# CH32F207VCT6-R0.net
KiCad netlist of a schematic drawn in Altium Designer
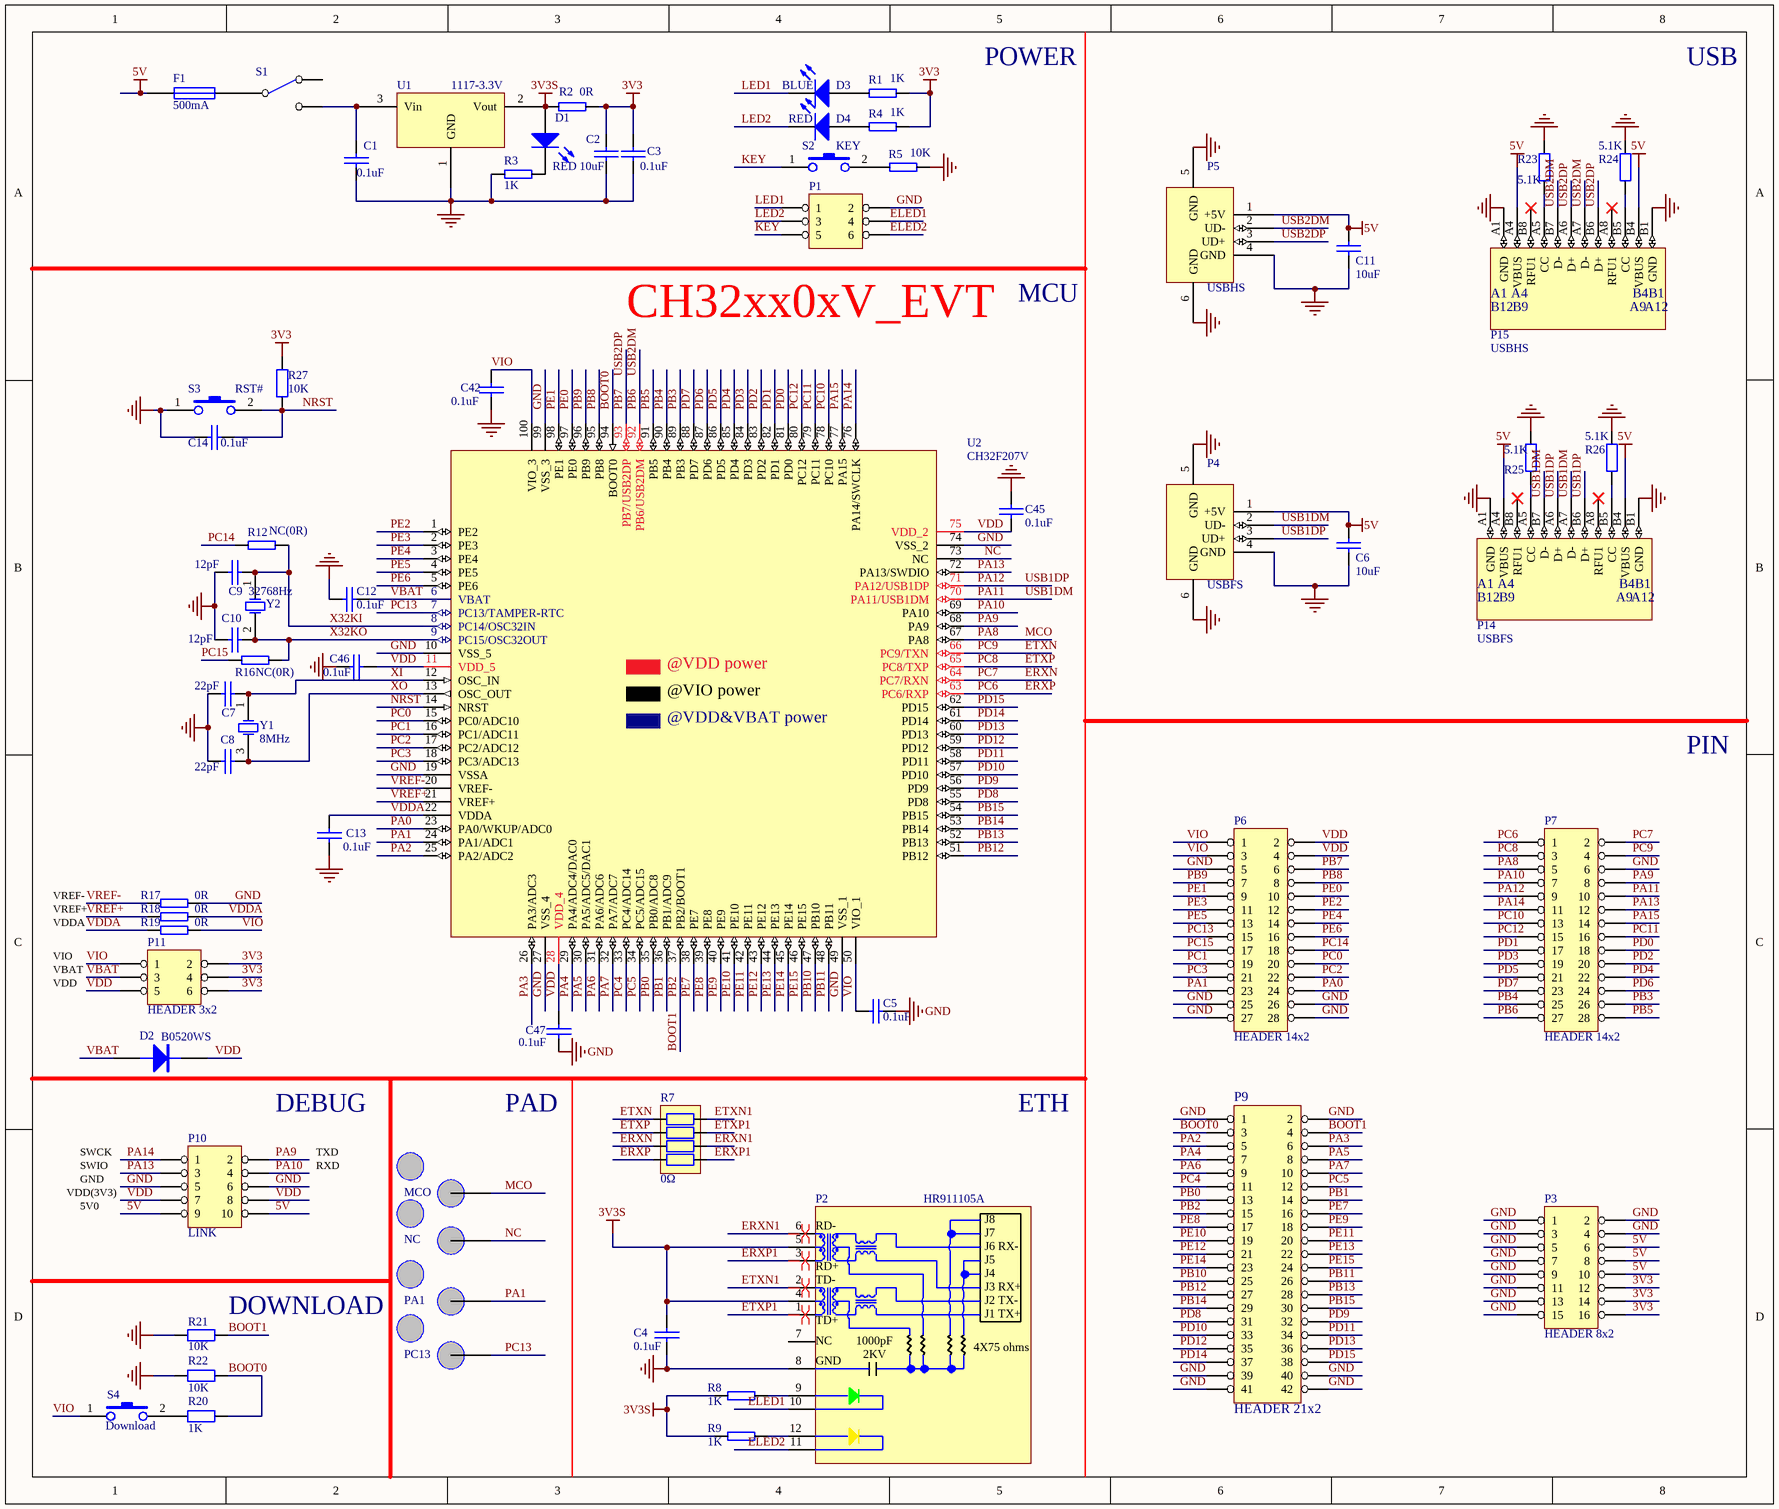
[diagram p0: CH32F207VCT6-R0.SchDoc]

(export (version "E")
  (design (tool "Eeschema 10.0.6"))
  (components
    (comp (ref "C1")
      (value "0.1uF")
      (footprint "0603_C")
      (description "Capacitor")
      (libsource (lib "*") (part "CAP"))
    )
    (comp (ref "C2")
      (value "10uF")
      (footprint "3216_C")
      (description "Capacitor")
      (libsource (lib "*") (part "CAP"))
    )
    (comp (ref "C3")
      (value "0.1uF")
      (footprint "0603_C")
      (description "Capacitor")
      (libsource (lib "*") (part "CAP"))
    )
    (comp (ref "C4")
      (value "0.1uF")
      (footprint "0603_C")
      (description "Capacitor")
      (libsource (lib "*") (part "CAP"))
    )
    (comp (ref "C5")
      (value "0.1uF")
      (footprint "0603_C")
      (description "Capacitor")
      (libsource (lib "*") (part "CAP"))
    )
    (comp (ref "C6")
      (value "10uF")
      (footprint "3216_C")
      (description "Capacitor")
      (libsource (lib "") (part "CAP_1"))
    )
    (comp (ref "C7")
      (value "22pF")
      (footprint "0603_C")
      (description "Capacitor")
      (libsource (lib "*") (part "CAP"))
    )
    (comp (ref "C8")
      (value "22pF")
      (footprint "0603_C")
      (description "Capacitor")
      (libsource (lib "*") (part "CAP"))
    )
    (comp (ref "C9")
      (value "12pF")
      (footprint "0603_C")
      (description "Capacitor")
      (libsource (lib "*") (part "CAP"))
    )
    (comp (ref "C10")
      (value "12pF")
      (footprint "0603_C")
      (description "Capacitor")
      (libsource (lib "*") (part "CAP"))
    )
    (comp (ref "C11")
      (value "10uF")
      (footprint "3216_C")
      (description "Capacitor")
      (libsource (lib "") (part "CAP_1"))
    )
    (comp (ref "C12")
      (value "0.1uF")
      (footprint "0603_C")
      (description "Capacitor")
      (libsource (lib "*") (part "CAP"))
    )
    (comp (ref "C13")
      (value "0.1uF")
      (footprint "0603_C")
      (description "Capacitor")
      (libsource (lib "*") (part "CAP"))
    )
    (comp (ref "C14")
      (value "0.1uF")
      (footprint "0603_C")
      (description "Capacitor")
      (libsource (lib "") (part "CAP_1"))
    )
    (comp (ref "C42")
      (value "0.1uF")
      (footprint "0603_C")
      (description "Capacitor")
      (libsource (lib "*") (part "CAP"))
    )
    (comp (ref "C45")
      (value "0.1uF")
      (footprint "0603_C")
      (description "Capacitor")
      (libsource (lib "*") (part "CAP"))
    )
    (comp (ref "C46")
      (value "0.1uF")
      (footprint "0603_C")
      (description "Capacitor")
      (libsource (lib "*") (part "CAP"))
    )
    (comp (ref "C47")
      (value "0.1uF")
      (footprint "0603_C")
      (description "Capacitor")
      (libsource (lib "*") (part "CAP"))
    )
    (comp (ref "D1")
      (value "RED")
      (footprint "0603+")
      (description "Typical INFRARED GaAs LED")
      (fields (field (name "PUBLISHER") "Altium Limited"))
      (libsource (lib "*") (part "LED0"))
    )
    (comp (ref "D2")
      (value "B0520WS")
      (footprint "SOD-323")
      (description "Diode")
      (libsource (lib "*") (part "DIODE"))
    )
    (comp (ref "D3")
      (value "BLUE")
      (footprint "0603+")
      (description "Typical INFRARED GaAs LED")
      (fields (field (name "PUBLISHER") "Altium Limited"))
      (libsource (lib "*") (part "LED0"))
    )
    (comp (ref "D4")
      (value "RED")
      (footprint "0603+")
      (description "Typical INFRARED GaAs LED")
      (fields (field (name "PUBLISHER") "Altium Limited"))
      (libsource (lib "*") (part "LED0"))
    )
    (comp (ref "F1")
      (value "500mA")
      (footprint "0805")
      (description "Fuse")
      (libsource (lib "wch_sch_others") (part "FUSE1"))
    )
    (comp (ref "MCO")
      (value "Testpoint")
      (footprint "TESTPOINT1")
      (description "测试点")
      (libsource (lib "wch_sch_others") (part "Testpoint"))
    )
    (comp (ref "NC")
      (value "Testpoint")
      (footprint "TESTPOINT1")
      (description "测试点")
      (libsource (lib "wch_sch_others") (part "Testpoint"))
    )
    (comp (ref "P1")
      (value "IO")
      (footprint "MYPCB:IDC6-2.54mm")
      (description "Header, 3-Pin, Dual row")
      (libsource (lib "wch_sch_others") (part "HEADER 3x2"))
    )
    (comp (ref "P2") (value "HR911105A") (footprint "HR911105A") (libsource (lib "*") (part "HR911105A")))
    (comp (ref "P3")
      (value "HEADER 8x2")
      (footprint "MYPCB:IDC16-2.54mm")
      (description "Header, 8-Pin, Dual row")
      (libsource (lib "wch_sch_others") (part "HEADER 8x2"))
    )
    (comp (ref "P4")
      (value "USBFS")
      (footprint "USBAF")
      (description "USB Port")
      (libsource (lib "*") (part "USB"))
    )
    (comp (ref "P5")
      (value "USBHS")
      (footprint "USBAF")
      (description "USB Port")
      (libsource (lib "*") (part "USB"))
    )
    (comp (ref "P6")
      (value "HEADER 14x2")
      (footprint "MYPCB:IDC28-2.54MM")
      (description "Header, 14-Pin, Dual row")
      (libsource (lib "wch_sch_others") (part "HEADER 14x2"))
    )
    (comp (ref "P7")
      (value "HEADER 14x2")
      (footprint "MYPCB:IDC28-2.54MM")
      (description "Header, 14-Pin, Dual row")
      (libsource (lib "wch_sch_others") (part "HEADER 14x2"))
    )
    (comp (ref "P9")
      (value "HEADER 21x2")
      (footprint "MYPCB:IDC42-2.54MM")
      (description "Header, 21-Pin, Dual row")
      (libsource (lib "wch_sch_others") (part "HEADER 21x2"))
    )
    (comp (ref "P10")
      (value "LINK")
      (footprint "MYPCB:IDC10-2.54mm")
      (description "Header, 5-Pin, Dual row")
      (libsource (lib "wch_sch_others") (part "HEADER 5x2"))
    )
    (comp (ref "P11")
      (value "HEADER 3x2")
      (footprint "MYPCB:IDC6-2.54mm")
      (description "Header, 3-Pin, Dual row")
      (libsource (lib "wch_sch_others") (part "HEADER 3x2"))
    )
    (comp (ref "P14")
      (value "USBFS")
      (footprint "TYPE-C-Receptacle-2.0")
      (libsource (lib "*") (part "TYPE-C1"))
    )
    (comp (ref "P15")
      (value "USBHS")
      (footprint "TYPE-C-Receptacle-2.0")
      (libsource (lib "*") (part "TYPE-C1"))
    )
    (comp (ref "PA1")
      (value "Testpoint")
      (footprint "TESTPOINT1")
      (description "测试点")
      (libsource (lib "wch_sch_others") (part "Testpoint"))
    )
    (comp (ref "PC13")
      (value "Testpoint")
      (footprint "TESTPOINT1")
      (description "测试点")
      (libsource (lib "wch_sch_others") (part "Testpoint"))
    )
    (comp (ref "R1") (value "1K") (footprint "0603") (libsource (lib "wch_sch_others") (part "RES")))
    (comp (ref "R2") (value "0R") (footprint "0603") (libsource (lib "wch_sch_others") (part "RES")))
    (comp (ref "R3") (value "1K") (footprint "0603") (libsource (lib "wch_sch_others") (part "RES")))
    (comp (ref "R4") (value "1K") (footprint "0603") (libsource (lib "wch_sch_others") (part "RES")))
    (comp (ref "R5") (value "10K") (footprint "0603") (libsource (lib "wch_sch_others") (part "RES")))
    (comp (ref "R7")
      (value "0Ω")
      (footprint "RCA-8P4R-0603")
      (description "贴片网络排阻")
      (fields (field (name "版权归属") "源创客"))
      (libsource (lib "wch_sch_others") (part "R-8P4R"))
    )
    (comp (ref "R8") (value "1K") (footprint "0603") (libsource (lib "wch_sch_others") (part "RES")))
    (comp (ref "R9") (value "1K") (footprint "0603") (libsource (lib "wch_sch_others") (part "RES")))
    (comp (ref "R12") (value "NC(0R)") (footprint "0603") (libsource (lib "wch_sch_others") (part "RES")))
    (comp (ref "R16") (value "NC(0R)") (footprint "0603") (libsource (lib "wch_sch_others") (part "RES")))
    (comp (ref "R17") (value "0R") (footprint "0603") (libsource (lib "*") (part "R")))
    (comp (ref "R18") (value "0R") (footprint "0603") (libsource (lib "*") (part "R")))
    (comp (ref "R19") (value "0R") (footprint "0603") (libsource (lib "*") (part "R")))
    (comp (ref "R20")
      (value "1K")
      (footprint "0603")
      (description "Resistor")
      (fields (field (name "PUBLISHER") "Altium Limited"))
      (libsource (lib "Miscellaneous Devices") (part "Res2"))
    )
    (comp (ref "R21")
      (value "10K")
      (footprint "0603")
      (description "Resistor")
      (fields (field (name "PUBLISHER") "Altium Limited"))
      (libsource (lib "Miscellaneous Devices") (part "Res2"))
    )
    (comp (ref "R22")
      (value "10K")
      (footprint "0603")
      (description "Resistor")
      (fields (field (name "PUBLISHER") "Altium Limited"))
      (libsource (lib "Miscellaneous Devices") (part "Res2"))
    )
    (comp (ref "R23")
      (value "5.1K")
      (footprint "0603")
      (description "Resistor")
      (libsource (lib "") (part "Res2_1"))
    )
    (comp (ref "R24")
      (value "5.1K")
      (footprint "0603")
      (description "Resistor")
      (libsource (lib "") (part "Res2_1"))
    )
    (comp (ref "R25")
      (value "5.1K")
      (footprint "0603")
      (description "Resistor")
      (libsource (lib "") (part "Res2_1"))
    )
    (comp (ref "R26")
      (value "5.1K")
      (footprint "0603")
      (description "Resistor")
      (libsource (lib "") (part "Res2_1"))
    )
    (comp (ref "R27")
      (value "10K")
      (footprint "0603")
      (description "Resistor")
      (fields (field (name "PUBLISHER") "Altium Limited"))
      (libsource (lib "") (part "Res2_1"))
    )
    (comp (ref "S1") (value "SW SPDT") (footprint "KEY2") (libsource (lib "*") (part "SW SPDT")))
    (comp (ref "S2")
      (value "KEY")
      (footprint "SMD_6.1x3.65x2.5mm-KEY")
      (libsource (lib "wch_sch_others") (part "KEY1"))
    )
    (comp (ref "S3")
      (value "RST#")
      (footprint "SMD_6.1x3.65x2.5mm-KEY")
      (libsource (lib "wch_sch_others") (part "KEY1"))
    )
    (comp (ref "S4")
      (value "Download")
      (footprint "SMD_6.1x3.65x2.5mm-KEY")
      (libsource (lib "wch_sch_others") (part "KEY1"))
    )
    (comp (ref "U1")
      (value "1117-3.3V")
      (footprint "SOT-223")
      (libsource (lib "wch_sch_others") (part "1117-3.3V"))
    )
    (comp (ref "U2")
      (value "CH32F207V")
      (footprint "LQFP100")
      (description "ARM M3 HD-MCU, 144MHz, USB_480M, USB OTG, 1000M Ethernet MAC, 2*CAN")
      (libsource (lib "CHXXX") (part "CH32F207V"))
    )
    (comp (ref "Y1")
      (value "8MHz")
      (footprint "XT3225")
      (description "Crystal Oscillator")
      (fields (field (name "PUBLISHER") "Altium Limited"))
      (libsource (lib "*") (part "XTAL"))
    )
    (comp (ref "Y2")
      (value "32768Hz")
      (footprint "FC-135")
      (description "Crystal Oscillator")
      (fields (field (name "PUBLISHER") "Altium Limited"))
      (libsource (lib "") (part "XTAL_1"))
    )
  )
  (nets
    (net (code "2") (name "/BOOT0") (class "Default")
      (node (ref "P9") (pin "3") (pinfunction "3_3") (pintype "passive"))
      (node (ref "R20") (pin "1") (pinfunction "1_1") (pintype "passive"))
      (node (ref "R22") (pin "1") (pinfunction "1_1") (pintype "passive"))
      (node (ref "U2") (pin "94") (pinfunction "BOOT0_94") (pintype "input"))
    )
    (net (code "3") (name "/BOOT1") (class "Default")
      (node (ref "P9") (pin "15") (pinfunction "15_15") (pintype "passive"))
      (node (ref "P9") (pin "4") (pinfunction "4_4") (pintype "passive"))
      (node (ref "R21") (pin "1") (pinfunction "1_1") (pintype "passive"))
      (node (ref "U2") (pin "37") (pinfunction "PB2/BOOT1_37") (pintype "bidirectional"))
    )
    (net (code "4") (name "/ELED1") (class "Default")
      (node (ref "P1") (pin "4") (pinfunction "4_4") (pintype "passive"))
      (node (ref "P2") (pin "10") (pintype "passive"))
    )
    (net (code "5") (name "/ELED2") (class "Default")
      (node (ref "P1") (pin "6") (pinfunction "6_6") (pintype "passive"))
      (node (ref "P2") (pin "11") (pintype "passive"))
    )
    (net (code "6") (name "/ERXN") (class "Default")
      (node (ref "P7") (pin "2") (pinfunction "2_2") (pintype "passive"))
      (node (ref "R7") (pin "3") (pinfunction "3_3") (pintype "passive"))
      (node (ref "U2") (pin "64") (pinfunction "PC7/RXN_64") (pintype "bidirectional"))
    )
    (net (code "7") (name "/ERXN1") (class "Default")
      (node (ref "P2") (pin "6") (pintype "passive"))
      (node (ref "R7") (pin "6") (pinfunction "6_6") (pintype "passive"))
    )
    (net (code "8") (name "/ERXP") (class "Default")
      (node (ref "P7") (pin "1") (pinfunction "1_1") (pintype "passive"))
      (node (ref "R7") (pin "4") (pinfunction "4_4") (pintype "passive"))
      (node (ref "U2") (pin "63") (pinfunction "PC6/RXP_63") (pintype "bidirectional"))
    )
    (net (code "9") (name "/ERXP1") (class "Default")
      (node (ref "P2") (pin "3") (pintype "passive"))
      (node (ref "R7") (pin "5") (pinfunction "5_5") (pintype "passive"))
    )
    (net (code "10") (name "/ETXN") (class "Default")
      (node (ref "P7") (pin "4") (pinfunction "4_4") (pintype "passive"))
      (node (ref "R7") (pin "1") (pinfunction "1_1") (pintype "passive"))
      (node (ref "U2") (pin "66") (pinfunction "PC9/TXN_66") (pintype "bidirectional"))
    )
    (net (code "11") (name "/ETXN1") (class "Default")
      (node (ref "P2") (pin "2") (pintype "passive"))
      (node (ref "R7") (pin "8") (pinfunction "8_8") (pintype "passive"))
    )
    (net (code "12") (name "/ETXP") (class "Default")
      (node (ref "P7") (pin "3") (pinfunction "3_3") (pintype "passive"))
      (node (ref "R7") (pin "2") (pinfunction "2_2") (pintype "passive"))
      (node (ref "U2") (pin "65") (pinfunction "PC8/TXP_65") (pintype "bidirectional"))
    )
    (net (code "13") (name "/ETXP1") (class "Default")
      (node (ref "P2") (pin "1") (pintype "passive"))
      (node (ref "R7") (pin "7") (pinfunction "7_7") (pintype "passive"))
    )
    (net (code "14") (name "/KEY") (class "Default")
      (node (ref "P1") (pin "5") (pinfunction "5_5") (pintype "passive"))
      (node (ref "S2") (pin "1") (pinfunction "1_1") (pintype "passive"))
    )
    (net (code "15") (name "/LED1") (class "Default")
      (node (ref "D3") (pin "2") (pinfunction "K_2") (pintype "passive"))
      (node (ref "P1") (pin "1") (pinfunction "1_1") (pintype "passive"))
    )
    (net (code "16") (name "/LED2") (class "Default")
      (node (ref "D4") (pin "2") (pinfunction "K_2") (pintype "passive"))
      (node (ref "P1") (pin "3") (pinfunction "3_3") (pintype "passive"))
    )
    (net (code "17") (name "/MCO") (class "Default")
      (node (ref "MCO") (pin "1") (pinfunction "point_1") (pintype "passive"))
      (node (ref "P7") (pin "5") (pinfunction "5_5") (pintype "passive"))
      (node (ref "U2") (pin "67") (pinfunction "PA8_67") (pintype "bidirectional"))
    )
    (net (code "18") (name "/NC") (class "Default")
      (node (ref "NC") (pin "1") (pinfunction "point_1") (pintype "passive"))
      (node (ref "U2") (pin "73") (pinfunction "NC_73") (pintype "tri_state"))
    )
    (net (code "19") (name "/NRST") (class "Default")
      (node (ref "C14") (pin "2") (pinfunction "2_2") (pintype "passive"))
      (node (ref "R27") (pin "1") (pinfunction "1_1") (pintype "passive"))
      (node (ref "S3") (pin "2") (pinfunction "2_2") (pintype "passive"))
      (node (ref "U2") (pin "14") (pinfunction "NRST_14") (pintype "input"))
    )
    (net (code "20") (name "/PA0") (class "Default")
      (node (ref "P6") (pin "24") (pinfunction "24_24") (pintype "passive"))
      (node (ref "U2") (pin "23") (pinfunction "PA0/WKUP/ADC0_23") (pintype "bidirectional"))
    )
    (net (code "21") (name "/PA1") (class "Default")
      (node (ref "P6") (pin "23") (pinfunction "23_23") (pintype "passive"))
      (node (ref "PA1") (pin "1") (pinfunction "point_1") (pintype "passive"))
      (node (ref "U2") (pin "24") (pinfunction "PA1/ADC1_24") (pintype "bidirectional"))
    )
    (net (code "22") (name "/PA2") (class "Default")
      (node (ref "P9") (pin "5") (pinfunction "5_5") (pintype "passive"))
      (node (ref "U2") (pin "25") (pinfunction "PA2/ADC2_25") (pintype "bidirectional"))
    )
    (net (code "23") (name "/PA3") (class "Default")
      (node (ref "P9") (pin "6") (pinfunction "6_6") (pintype "passive"))
      (node (ref "U2") (pin "26") (pinfunction "PA3/ADC3_26") (pintype "bidirectional"))
    )
    (net (code "24") (name "/PA4") (class "Default")
      (node (ref "P9") (pin "7") (pinfunction "7_7") (pintype "passive"))
      (node (ref "U2") (pin "29") (pinfunction "PA4/ADC4/DAC0_29") (pintype "bidirectional"))
    )
    (net (code "25") (name "/PA5") (class "Default")
      (node (ref "P9") (pin "8") (pinfunction "8_8") (pintype "passive"))
      (node (ref "U2") (pin "30") (pinfunction "PA5/ADC5/DAC1_30") (pintype "bidirectional"))
    )
    (net (code "26") (name "/PA6") (class "Default")
      (node (ref "P9") (pin "9") (pinfunction "9_9") (pintype "passive"))
      (node (ref "U2") (pin "31") (pinfunction "PA6/ADC6_31") (pintype "bidirectional"))
    )
    (net (code "27") (name "/PA7") (class "Default")
      (node (ref "P9") (pin "10") (pinfunction "10_10") (pintype "passive"))
      (node (ref "U2") (pin "32") (pinfunction "PA7/ADC7_32") (pintype "bidirectional"))
    )
    (net (code "28") (name "/PA9") (class "Default")
      (node (ref "P10") (pin "2") (pinfunction "2_2") (pintype "passive"))
      (node (ref "P7") (pin "8") (pinfunction "8_8") (pintype "passive"))
      (node (ref "U2") (pin "68") (pinfunction "PA9_68") (pintype "bidirectional"))
    )
    (net (code "29") (name "/PA10") (class "Default")
      (node (ref "P10") (pin "4") (pinfunction "4_4") (pintype "passive"))
      (node (ref "P7") (pin "7") (pinfunction "7_7") (pintype "passive"))
      (node (ref "U2") (pin "69") (pinfunction "PA10_69") (pintype "bidirectional"))
    )
    (net (code "30") (name "/PA11") (class "Default")
      (node (ref "P14") (pin "A7") (pinfunction "D-_A7") (pintype "bidirectional"))
      (node (ref "P14") (pin "B7") (pinfunction "D-_B7") (pintype "bidirectional"))
      (node (ref "P4") (pin "2") (pinfunction "UD-_2") (pintype "bidirectional"))
      (node (ref "P7") (pin "10") (pinfunction "10_10") (pintype "passive"))
      (node (ref "U2") (pin "70") (pinfunction "PA11/USB1DM_70") (pintype "bidirectional"))
    )
    (net (code "31") (name "/PA12") (class "Default")
      (node (ref "P14") (pin "A6") (pinfunction "D+_A6") (pintype "bidirectional"))
      (node (ref "P14") (pin "B6") (pinfunction "D+_B6") (pintype "bidirectional"))
      (node (ref "P4") (pin "3") (pinfunction "UD+_3") (pintype "bidirectional"))
      (node (ref "P7") (pin "9") (pinfunction "9_9") (pintype "passive"))
      (node (ref "U2") (pin "71") (pinfunction "PA12/USB1DP_71") (pintype "bidirectional"))
    )
    (net (code "32") (name "/PA13") (class "Default")
      (node (ref "P10") (pin "3") (pinfunction "3_3") (pintype "passive"))
      (node (ref "P7") (pin "12") (pinfunction "12_12") (pintype "passive"))
      (node (ref "U2") (pin "72") (pinfunction "PA13/SWDIO_72") (pintype "bidirectional"))
    )
    (net (code "33") (name "/PA14") (class "Default")
      (node (ref "P10") (pin "1") (pinfunction "1_1") (pintype "passive"))
      (node (ref "P7") (pin "11") (pinfunction "11_11") (pintype "passive"))
      (node (ref "U2") (pin "76") (pinfunction "PA14/SWCLK_76") (pintype "bidirectional"))
    )
    (net (code "34") (name "/PA15") (class "Default")
      (node (ref "P7") (pin "14") (pinfunction "14_14") (pintype "passive"))
      (node (ref "U2") (pin "77") (pinfunction "PA15_77") (pintype "bidirectional"))
    )
    (net (code "35") (name "/PB0") (class "Default")
      (node (ref "P9") (pin "13") (pinfunction "13_13") (pintype "passive"))
      (node (ref "U2") (pin "35") (pinfunction "PB0/ADC8_35") (pintype "bidirectional"))
    )
    (net (code "36") (name "/PB1") (class "Default")
      (node (ref "P9") (pin "14") (pinfunction "14_14") (pintype "passive"))
      (node (ref "U2") (pin "36") (pinfunction "PB1/ADC9_36") (pintype "bidirectional"))
    )
    (net (code "37") (name "/PB3") (class "Default")
      (node (ref "P7") (pin "26") (pinfunction "26_26") (pintype "passive"))
      (node (ref "U2") (pin "89") (pinfunction "PB3_89") (pintype "bidirectional"))
    )
    (net (code "38") (name "/PB4") (class "Default")
      (node (ref "P7") (pin "25") (pinfunction "25_25") (pintype "passive"))
      (node (ref "U2") (pin "90") (pinfunction "PB4_90") (pintype "bidirectional"))
    )
    (net (code "39") (name "/PB5") (class "Default")
      (node (ref "P7") (pin "28") (pinfunction "28_28") (pintype "passive"))
      (node (ref "U2") (pin "91") (pinfunction "PB5_91") (pintype "bidirectional"))
    )
    (net (code "40") (name "/PB6") (class "Default")
      (node (ref "P15") (pin "A7") (pinfunction "D-_A7") (pintype "bidirectional"))
      (node (ref "P15") (pin "B7") (pinfunction "D-_B7") (pintype "bidirectional"))
      (node (ref "P5") (pin "2") (pinfunction "UD-_2") (pintype "bidirectional"))
      (node (ref "P7") (pin "27") (pinfunction "27_27") (pintype "passive"))
      (node (ref "U2") (pin "92") (pinfunction "PB6/USB2DM_92") (pintype "bidirectional"))
    )
    (net (code "41") (name "/PB7") (class "Default")
      (node (ref "P15") (pin "A6") (pinfunction "D+_A6") (pintype "bidirectional"))
      (node (ref "P15") (pin "B6") (pinfunction "D+_B6") (pintype "bidirectional"))
      (node (ref "P5") (pin "3") (pinfunction "UD+_3") (pintype "bidirectional"))
      (node (ref "P6") (pin "6") (pinfunction "6_6") (pintype "passive"))
      (node (ref "U2") (pin "93") (pinfunction "PB7/USB2DP_93") (pintype "bidirectional"))
    )
    (net (code "42") (name "/PB8") (class "Default")
      (node (ref "P6") (pin "8") (pinfunction "8_8") (pintype "passive"))
      (node (ref "U2") (pin "95") (pinfunction "PB8_95") (pintype "bidirectional"))
    )
    (net (code "43") (name "/PB9") (class "Default")
      (node (ref "P6") (pin "7") (pinfunction "7_7") (pintype "passive"))
      (node (ref "U2") (pin "96") (pinfunction "PB9_96") (pintype "bidirectional"))
    )
    (net (code "44") (name "/PB10") (class "Default")
      (node (ref "P9") (pin "25") (pinfunction "25_25") (pintype "passive"))
      (node (ref "U2") (pin "47") (pinfunction "PB10_47") (pintype "bidirectional"))
    )
    (net (code "45") (name "/PB11") (class "Default")
      (node (ref "P9") (pin "26") (pinfunction "26_26") (pintype "passive"))
      (node (ref "U2") (pin "48") (pinfunction "PB11_48") (pintype "bidirectional"))
    )
    (net (code "46") (name "/PB12") (class "Default")
      (node (ref "P9") (pin "27") (pinfunction "27_27") (pintype "passive"))
      (node (ref "U2") (pin "51") (pinfunction "PB12_51") (pintype "bidirectional"))
    )
    (net (code "47") (name "/PB13") (class "Default")
      (node (ref "P9") (pin "28") (pinfunction "28_28") (pintype "passive"))
      (node (ref "U2") (pin "52") (pinfunction "PB13_52") (pintype "bidirectional"))
    )
    (net (code "48") (name "/PB14") (class "Default")
      (node (ref "P9") (pin "29") (pinfunction "29_29") (pintype "passive"))
      (node (ref "U2") (pin "53") (pinfunction "PB14_53") (pintype "bidirectional"))
    )
    (net (code "49") (name "/PB15") (class "Default")
      (node (ref "P9") (pin "30") (pinfunction "30_30") (pintype "passive"))
      (node (ref "U2") (pin "54") (pinfunction "PB15_54") (pintype "bidirectional"))
    )
    (net (code "50") (name "/PC0") (class "Default")
      (node (ref "P6") (pin "20") (pinfunction "20_20") (pintype "passive"))
      (node (ref "U2") (pin "15") (pinfunction "PC0/ADC10_15") (pintype "bidirectional"))
    )
    (net (code "51") (name "/PC1") (class "Default")
      (node (ref "P6") (pin "19") (pinfunction "19_19") (pintype "passive"))
      (node (ref "U2") (pin "16") (pinfunction "PC1/ADC11_16") (pintype "bidirectional"))
    )
    (net (code "52") (name "/PC2") (class "Default")
      (node (ref "P6") (pin "22") (pinfunction "22_22") (pintype "passive"))
      (node (ref "U2") (pin "17") (pinfunction "PC2/ADC12_17") (pintype "bidirectional"))
    )
    (net (code "53") (name "/PC3") (class "Default")
      (node (ref "P6") (pin "21") (pinfunction "21_21") (pintype "passive"))
      (node (ref "U2") (pin "18") (pinfunction "PC3/ADC13_18") (pintype "bidirectional"))
    )
    (net (code "54") (name "/PC4") (class "Default")
      (node (ref "P9") (pin "11") (pinfunction "11_11") (pintype "passive"))
      (node (ref "U2") (pin "33") (pinfunction "PC4/ADC14_33") (pintype "bidirectional"))
    )
    (net (code "55") (name "/PC5") (class "Default")
      (node (ref "P9") (pin "12") (pinfunction "12_12") (pintype "passive"))
      (node (ref "U2") (pin "34") (pinfunction "PC5/ADC15_34") (pintype "bidirectional"))
    )
    (net (code "56") (name "/PC10") (class "Default")
      (node (ref "P7") (pin "13") (pinfunction "13_13") (pintype "passive"))
      (node (ref "U2") (pin "78") (pinfunction "PC10_78") (pintype "bidirectional"))
    )
    (net (code "57") (name "/PC11") (class "Default")
      (node (ref "P7") (pin "16") (pinfunction "16_16") (pintype "passive"))
      (node (ref "U2") (pin "79") (pinfunction "PC11_79") (pintype "bidirectional"))
    )
    (net (code "58") (name "/PC12") (class "Default")
      (node (ref "P7") (pin "15") (pinfunction "15_15") (pintype "passive"))
      (node (ref "U2") (pin "80") (pinfunction "PC12_80") (pintype "bidirectional"))
    )
    (net (code "59") (name "/PC13") (class "Default")
      (node (ref "P6") (pin "15") (pinfunction "15_15") (pintype "passive"))
      (node (ref "PC13") (pin "1") (pinfunction "point_1") (pintype "passive"))
      (node (ref "U2") (pin "7") (pinfunction "PC13/TAMPER-RTC_7") (pintype "bidirectional"))
    )
    (net (code "60") (name "/PC14") (class "Default")
      (node (ref "P6") (pin "18") (pinfunction "18_18") (pintype "passive"))
      (node (ref "R12") (pin "1") (pintype "passive"))
    )
    (net (code "61") (name "/PC15") (class "Default")
      (node (ref "P6") (pin "17") (pinfunction "17_17") (pintype "passive"))
      (node (ref "R16") (pin "1") (pintype "passive"))
    )
    (net (code "62") (name "/PD0") (class "Default")
      (node (ref "P7") (pin "18") (pinfunction "18_18") (pintype "passive"))
      (node (ref "U2") (pin "81") (pinfunction "PD0_81") (pintype "bidirectional"))
    )
    (net (code "63") (name "/PD1") (class "Default")
      (node (ref "P7") (pin "17") (pinfunction "17_17") (pintype "passive"))
      (node (ref "U2") (pin "82") (pinfunction "PD1_82") (pintype "bidirectional"))
    )
    (net (code "64") (name "/PD2") (class "Default")
      (node (ref "P7") (pin "20") (pinfunction "20_20") (pintype "passive"))
      (node (ref "U2") (pin "83") (pinfunction "PD2_83") (pintype "bidirectional"))
    )
    (net (code "65") (name "/PD3") (class "Default")
      (node (ref "P7") (pin "19") (pinfunction "19_19") (pintype "passive"))
      (node (ref "U2") (pin "84") (pinfunction "PD3_84") (pintype "bidirectional"))
    )
    (net (code "66") (name "/PD4") (class "Default")
      (node (ref "P7") (pin "22") (pinfunction "22_22") (pintype "passive"))
      (node (ref "U2") (pin "85") (pinfunction "PD4_85") (pintype "bidirectional"))
    )
    (net (code "67") (name "/PD5") (class "Default")
      (node (ref "P7") (pin "21") (pinfunction "21_21") (pintype "passive"))
      (node (ref "U2") (pin "86") (pinfunction "PD5_86") (pintype "bidirectional"))
    )
    (net (code "68") (name "/PD6") (class "Default")
      (node (ref "P7") (pin "24") (pinfunction "24_24") (pintype "passive"))
      (node (ref "U2") (pin "87") (pinfunction "PD6_87") (pintype "bidirectional"))
    )
    (net (code "69") (name "/PD7") (class "Default")
      (node (ref "P7") (pin "23") (pinfunction "23_23") (pintype "passive"))
      (node (ref "U2") (pin "88") (pinfunction "PD7_88") (pintype "bidirectional"))
    )
    (net (code "70") (name "/PD8") (class "Default")
      (node (ref "P9") (pin "31") (pinfunction "31_31") (pintype "passive"))
      (node (ref "U2") (pin "55") (pinfunction "PD8_55") (pintype "bidirectional"))
    )
    (net (code "71") (name "/PD9") (class "Default")
      (node (ref "P9") (pin "32") (pinfunction "32_32") (pintype "passive"))
      (node (ref "U2") (pin "56") (pinfunction "PD9_56") (pintype "bidirectional"))
    )
    (net (code "72") (name "/PD10") (class "Default")
      (node (ref "P9") (pin "33") (pinfunction "33_33") (pintype "passive"))
      (node (ref "U2") (pin "57") (pinfunction "PD10_57") (pintype "bidirectional"))
    )
    (net (code "73") (name "/PD11") (class "Default")
      (node (ref "P9") (pin "34") (pinfunction "34_34") (pintype "passive"))
      (node (ref "U2") (pin "58") (pinfunction "PD11_58") (pintype "bidirectional"))
    )
    (net (code "74") (name "/PD12") (class "Default")
      (node (ref "P9") (pin "35") (pinfunction "35_35") (pintype "passive"))
      (node (ref "U2") (pin "59") (pinfunction "PD12_59") (pintype "bidirectional"))
    )
    (net (code "75") (name "/PD13") (class "Default")
      (node (ref "P9") (pin "36") (pinfunction "36_36") (pintype "passive"))
      (node (ref "U2") (pin "60") (pinfunction "PD13_60") (pintype "bidirectional"))
    )
    (net (code "76") (name "/PD14") (class "Default")
      (node (ref "P9") (pin "37") (pinfunction "37_37") (pintype "passive"))
      (node (ref "U2") (pin "61") (pinfunction "PD14_61") (pintype "bidirectional"))
    )
    (net (code "77") (name "/PD15") (class "Default")
      (node (ref "P9") (pin "38") (pinfunction "38_38") (pintype "passive"))
      (node (ref "U2") (pin "62") (pinfunction "PD15_62") (pintype "bidirectional"))
    )
    (net (code "78") (name "/PE0") (class "Default")
      (node (ref "P6") (pin "10") (pinfunction "10_10") (pintype "passive"))
      (node (ref "U2") (pin "97") (pinfunction "PE0_97") (pintype "bidirectional"))
    )
    (net (code "79") (name "/PE1") (class "Default")
      (node (ref "P6") (pin "9") (pinfunction "9_9") (pintype "passive"))
      (node (ref "U2") (pin "98") (pinfunction "PE1_98") (pintype "bidirectional"))
    )
    (net (code "80") (name "/PE2") (class "Default")
      (node (ref "P6") (pin "12") (pinfunction "12_12") (pintype "passive"))
      (node (ref "U2") (pin "1") (pinfunction "PE2_1") (pintype "bidirectional"))
    )
    (net (code "81") (name "/PE3") (class "Default")
      (node (ref "P6") (pin "11") (pinfunction "11_11") (pintype "passive"))
      (node (ref "U2") (pin "2") (pinfunction "PE3_2") (pintype "bidirectional"))
    )
    (net (code "82") (name "/PE4") (class "Default")
      (node (ref "P6") (pin "14") (pinfunction "14_14") (pintype "passive"))
      (node (ref "U2") (pin "3") (pinfunction "PE4_3") (pintype "bidirectional"))
    )
    (net (code "83") (name "/PE5") (class "Default")
      (node (ref "P6") (pin "13") (pinfunction "13_13") (pintype "passive"))
      (node (ref "U2") (pin "4") (pinfunction "PE5_4") (pintype "bidirectional"))
    )
    (net (code "84") (name "/PE6") (class "Default")
      (node (ref "P6") (pin "16") (pinfunction "16_16") (pintype "passive"))
      (node (ref "U2") (pin "5") (pinfunction "PE6_5") (pintype "bidirectional"))
    )
    (net (code "85") (name "/PE7") (class "Default")
      (node (ref "P9") (pin "16") (pinfunction "16_16") (pintype "passive"))
      (node (ref "U2") (pin "38") (pinfunction "PE7_38") (pintype "bidirectional"))
    )
    (net (code "86") (name "/PE8") (class "Default")
      (node (ref "P9") (pin "17") (pinfunction "17_17") (pintype "passive"))
      (node (ref "U2") (pin "39") (pinfunction "PE8_39") (pintype "bidirectional"))
    )
    (net (code "87") (name "/PE9") (class "Default")
      (node (ref "P9") (pin "18") (pinfunction "18_18") (pintype "passive"))
      (node (ref "U2") (pin "40") (pinfunction "PE9_40") (pintype "bidirectional"))
    )
    (net (code "88") (name "/PE10") (class "Default")
      (node (ref "P9") (pin "19") (pinfunction "19_19") (pintype "passive"))
      (node (ref "U2") (pin "41") (pinfunction "PE10_41") (pintype "bidirectional"))
    )
    (net (code "89") (name "/PE11") (class "Default")
      (node (ref "P9") (pin "20") (pinfunction "20_20") (pintype "passive"))
      (node (ref "U2") (pin "42") (pinfunction "PE11_42") (pintype "bidirectional"))
    )
    (net (code "90") (name "/PE12") (class "Default")
      (node (ref "P9") (pin "21") (pinfunction "21_21") (pintype "passive"))
      (node (ref "U2") (pin "43") (pinfunction "PE12_43") (pintype "bidirectional"))
    )
    (net (code "91") (name "/PE13") (class "Default")
      (node (ref "P9") (pin "22") (pinfunction "22_22") (pintype "passive"))
      (node (ref "U2") (pin "44") (pinfunction "PE13_44") (pintype "bidirectional"))
    )
    (net (code "92") (name "/PE14") (class "Default")
      (node (ref "P9") (pin "23") (pinfunction "23_23") (pintype "passive"))
      (node (ref "U2") (pin "45") (pinfunction "PE14_45") (pintype "bidirectional"))
    )
    (net (code "93") (name "/PE15") (class "Default")
      (node (ref "P9") (pin "24") (pinfunction "24_24") (pintype "passive"))
      (node (ref "U2") (pin "46") (pinfunction "PE15_46") (pintype "bidirectional"))
    )
    (net (code "94") (name "/VBAT") (class "Default")
      (node (ref "C12") (pin "2") (pinfunction "2_2") (pintype "passive"))
      (node (ref "D2") (pin "1") (pinfunction "A_1") (pintype "passive"))
      (node (ref "P11") (pin "3") (pinfunction "3_3") (pintype "passive"))
      (node (ref "U2") (pin "6") (pinfunction "VBAT_6") (pintype "power_in"))
    )
    (net (code "95") (name "/VDD") (class "Default")
      (node (ref "C45") (pin "1") (pinfunction "1_1") (pintype "passive"))
      (node (ref "C46") (pin "1") (pinfunction "1_1") (pintype "passive"))
      (node (ref "C47") (pin "2") (pinfunction "2_2") (pintype "passive"))
      (node (ref "D2") (pin "2") (pinfunction "K_2") (pintype "passive"))
      (node (ref "P10") (pin "7") (pinfunction "7_7") (pintype "passive"))
      (node (ref "P10") (pin "8") (pinfunction "8_8") (pintype "passive"))
      (node (ref "P11") (pin "5") (pinfunction "5_5") (pintype "passive"))
      (node (ref "P6") (pin "2") (pinfunction "2_2") (pintype "passive"))
      (node (ref "P6") (pin "4") (pinfunction "4_4") (pintype "passive"))
      (node (ref "U2") (pin "11") (pinfunction "VDD_5_11") (pintype "power_in"))
      (node (ref "U2") (pin "28") (pinfunction "VDD_4_28") (pintype "power_in"))
      (node (ref "U2") (pin "75") (pinfunction "VDD_2_75") (pintype "power_in"))
    )
    (net (code "96") (name "/VDDA") (class "Default")
      (node (ref "C13") (pin "1") (pinfunction "1_1") (pintype "passive"))
      (node (ref "R18") (pin "1") (pinfunction "1_1") (pintype "passive"))
      (node (ref "R19") (pin "2") (pinfunction "2_2") (pintype "passive"))
      (node (ref "U2") (pin "22") (pinfunction "VDDA_22") (pintype "power_in"))
    )
    (net (code "97") (name "/VIO") (class "Default")
      (node (ref "C42") (pin "2") (pinfunction "2_2") (pintype "passive"))
      (node (ref "C5") (pin "1") (pinfunction "1_1") (pintype "passive"))
      (node (ref "P11") (pin "1") (pinfunction "1_1") (pintype "passive"))
      (node (ref "P6") (pin "1") (pinfunction "1_1") (pintype "passive"))
      (node (ref "P6") (pin "3") (pinfunction "3_3") (pintype "passive"))
      (node (ref "R19") (pin "1") (pinfunction "1_1") (pintype "passive"))
      (node (ref "S4") (pin "1") (pinfunction "1_1") (pintype "passive"))
      (node (ref "U2") (pin "100") (pinfunction "VIO_3_100") (pintype "power_in"))
      (node (ref "U2") (pin "50") (pinfunction "VIO_1_50") (pintype "power_in"))
    )
    (net (code "98") (name "/VREF+") (class "Default")
      (node (ref "R18") (pin "2") (pinfunction "2_2") (pintype "passive"))
      (node (ref "U2") (pin "21") (pinfunction "VREF+_21") (pintype "power_in"))
    )
    (net (code "99") (name "/VREF-") (class "Default")
      (node (ref "R17") (pin "2") (pinfunction "2_2") (pintype "passive"))
      (node (ref "U2") (pin "20") (pinfunction "VREF-_20") (pintype "power_in"))
    )
    (net (code "100") (name "/X32KI") (class "Default")
      (node (ref "C9") (pin "2") (pinfunction "2_2") (pintype "passive"))
      (node (ref "R12") (pin "2") (pintype "passive"))
      (node (ref "U2") (pin "8") (pinfunction "PC14/OSC32IN_8") (pintype "bidirectional"))
      (node (ref "Y2") (pin "1") (pinfunction "OSC1_1") (pintype "passive"))
    )
    (net (code "101") (name "/X32KO") (class "Default")
      (node (ref "C10") (pin "2") (pinfunction "2_2") (pintype "passive"))
      (node (ref "R16") (pin "2") (pintype "passive"))
      (node (ref "U2") (pin "9") (pinfunction "PC15/OSC32OUT_9") (pintype "bidirectional"))
      (node (ref "Y2") (pin "2") (pinfunction "OSC2_2") (pintype "passive"))
    )
    (net (code "102") (name "/XI") (class "Default")
      (node (ref "C7") (pin "2") (pinfunction "2_2") (pintype "passive"))
      (node (ref "U2") (pin "12") (pinfunction "OSC_IN_12") (pintype "input"))
      (node (ref "Y1") (pin "1") (pinfunction "OSC1_1") (pintype "passive"))
    )
    (net (code "103") (name "/XO") (class "Default")
      (node (ref "C8") (pin "2") (pinfunction "2_2") (pintype "passive"))
      (node (ref "U2") (pin "13") (pinfunction "OSC_OUT_13") (pintype "output"))
      (node (ref "Y1") (pin "3") (pinfunction "OSC2_3") (pintype "passive"))
    )
    (net (code "104") (name "3V3") (class "Default")
      (node (ref "C2") (pin "1") (pinfunction "1_1") (pintype "passive"))
      (node (ref "C3") (pin "1") (pinfunction "1_1") (pintype "passive"))
      (node (ref "P11") (pin "2") (pinfunction "2_2") (pintype "passive"))
      (node (ref "P11") (pin "4") (pinfunction "4_4") (pintype "passive"))
      (node (ref "P11") (pin "6") (pinfunction "6_6") (pintype "passive"))
      (node (ref "P3") (pin "12") (pinfunction "12_12") (pintype "passive"))
      (node (ref "P3") (pin "14") (pinfunction "14_14") (pintype "passive"))
      (node (ref "P3") (pin "16") (pinfunction "16_16") (pintype "passive"))
      (node (ref "R1") (pin "1") (pintype "passive"))
      (node (ref "R2") (pin "1") (pintype "passive"))
      (node (ref "R27") (pin "2") (pinfunction "2_2") (pintype "passive"))
      (node (ref "R4") (pin "1") (pintype "passive"))
    )
    (net (code "105") (name "3V3S") (class "Default")
      (node (ref "C4") (pin "2") (pinfunction "2_2") (pintype "passive"))
      (node (ref "D1") (pin "1") (pinfunction "A_1") (pintype "passive"))
      (node (ref "P2") (pin "4") (pintype "passive"))
      (node (ref "P2") (pin "5") (pintype "passive"))
      (node (ref "R2") (pin "2") (pintype "passive"))
      (node (ref "R8") (pin "1") (pintype "passive"))
      (node (ref "R9") (pin "1") (pintype "passive"))
      (node (ref "U1") (pin "2") (pinfunction "Vout_2") (pintype "passive"))
    )
    (net (code "106") (name "5V") (class "Default")
      (node (ref "C11") (pin "1") (pinfunction "1_1") (pintype "passive"))
      (node (ref "C6") (pin "1") (pinfunction "1_1") (pintype "passive"))
      (node (ref "F1") (pin "1") (pinfunction "1_1") (pintype "passive"))
      (node (ref "P10") (pin "10") (pinfunction "10_10") (pintype "passive"))
      (node (ref "P10") (pin "9") (pinfunction "9_9") (pintype "passive"))
      (node (ref "P14") (pin "A4") (pinfunction "VBUS_A4") (pintype "bidirectional"))
      (node (ref "P14") (pin "B4") (pinfunction "VBUS_B4") (pintype "bidirectional"))
      (node (ref "P15") (pin "A4") (pinfunction "VBUS_A4") (pintype "bidirectional"))
      (node (ref "P15") (pin "B4") (pinfunction "VBUS_B4") (pintype "bidirectional"))
      (node (ref "P3") (pin "10") (pinfunction "10_10") (pintype "passive"))
      (node (ref "P3") (pin "6") (pinfunction "6_6") (pintype "passive"))
      (node (ref "P3") (pin "8") (pinfunction "8_8") (pintype "passive"))
      (node (ref "P4") (pin "1") (pinfunction "+5V_1") (pintype "power_in"))
      (node (ref "P5") (pin "1") (pinfunction "+5V_1") (pintype "power_in"))
    )
    (net (code "107") (name "GND") (class "Default")
      (node (ref "C1") (pin "2") (pinfunction "2_2") (pintype "passive"))
      (node (ref "C10") (pin "1") (pinfunction "1_1") (pintype "passive"))
      (node (ref "C11") (pin "2") (pinfunction "2_2") (pintype "passive"))
      (node (ref "C12") (pin "1") (pinfunction "1_1") (pintype "passive"))
      (node (ref "C13") (pin "2") (pinfunction "2_2") (pintype "passive"))
      (node (ref "C14") (pin "1") (pinfunction "1_1") (pintype "passive"))
      (node (ref "C2") (pin "2") (pinfunction "2_2") (pintype "passive"))
      (node (ref "C3") (pin "2") (pinfunction "2_2") (pintype "passive"))
      (node (ref "C4") (pin "1") (pinfunction "1_1") (pintype "passive"))
      (node (ref "C42") (pin "1") (pinfunction "1_1") (pintype "passive"))
      (node (ref "C45") (pin "2") (pinfunction "2_2") (pintype "passive"))
      (node (ref "C46") (pin "2") (pinfunction "2_2") (pintype "passive"))
      (node (ref "C47") (pin "1") (pinfunction "1_1") (pintype "passive"))
      (node (ref "C5") (pin "2") (pinfunction "2_2") (pintype "passive"))
      (node (ref "C6") (pin "2") (pinfunction "2_2") (pintype "passive"))
      (node (ref "C7") (pin "1") (pinfunction "1_1") (pintype "passive"))
      (node (ref "C8") (pin "1") (pinfunction "1_1") (pintype "passive"))
      (node (ref "C9") (pin "1") (pinfunction "1_1") (pintype "passive"))
      (node (ref "P1") (pin "2") (pinfunction "2_2") (pintype "passive"))
      (node (ref "P10") (pin "5") (pinfunction "5_5") (pintype "passive"))
      (node (ref "P10") (pin "6") (pinfunction "6_6") (pintype "passive"))
      (node (ref "P14") (pin "A1") (pinfunction "GND_A1") (pintype "bidirectional"))
      (node (ref "P14") (pin "B1") (pinfunction "GND_B1") (pintype "bidirectional"))
      (node (ref "P15") (pin "A1") (pinfunction "GND_A1") (pintype "bidirectional"))
      (node (ref "P15") (pin "B1") (pinfunction "GND_B1") (pintype "bidirectional"))
      (node (ref "P2") (pin "8") (pintype "passive"))
      (node (ref "P3") (pin "1") (pinfunction "1_1") (pintype "passive"))
      (node (ref "P3") (pin "11") (pinfunction "11_11") (pintype "passive"))
      (node (ref "P3") (pin "13") (pinfunction "13_13") (pintype "passive"))
      (node (ref "P3") (pin "15") (pinfunction "15_15") (pintype "passive"))
      (node (ref "P3") (pin "2") (pinfunction "2_2") (pintype "passive"))
      (node (ref "P3") (pin "3") (pinfunction "3_3") (pintype "passive"))
      (node (ref "P3") (pin "4") (pinfunction "4_4") (pintype "passive"))
      (node (ref "P3") (pin "5") (pinfunction "5_5") (pintype "passive"))
      (node (ref "P3") (pin "7") (pinfunction "7_7") (pintype "passive"))
      (node (ref "P3") (pin "9") (pinfunction "9_9") (pintype "passive"))
      (node (ref "P4") (pin "4") (pinfunction "GND_4") (pintype "power_in"))
      (node (ref "P4") (pin "5") (pinfunction "GND_5") (pintype "power_in"))
      (node (ref "P4") (pin "6") (pinfunction "GND_6") (pintype "power_in"))
      (node (ref "P5") (pin "4") (pinfunction "GND_4") (pintype "power_in"))
      (node (ref "P5") (pin "5") (pinfunction "GND_5") (pintype "power_in"))
      (node (ref "P5") (pin "6") (pinfunction "GND_6") (pintype "power_in"))
      (node (ref "P6") (pin "25") (pinfunction "25_25") (pintype "passive"))
      (node (ref "P6") (pin "26") (pinfunction "26_26") (pintype "passive"))
      (node (ref "P6") (pin "27") (pinfunction "27_27") (pintype "passive"))
      (node (ref "P6") (pin "28") (pinfunction "28_28") (pintype "passive"))
      (node (ref "P6") (pin "5") (pinfunction "5_5") (pintype "passive"))
      (node (ref "P7") (pin "6") (pinfunction "6_6") (pintype "passive"))
      (node (ref "P9") (pin "1") (pinfunction "1_1") (pintype "passive"))
      (node (ref "P9") (pin "2") (pinfunction "2_2") (pintype "passive"))
      (node (ref "P9") (pin "39") (pinfunction "39_39") (pintype "passive"))
      (node (ref "P9") (pin "40") (pinfunction "40_40") (pintype "passive"))
      (node (ref "P9") (pin "41") (pinfunction "41_41") (pintype "passive"))
      (node (ref "P9") (pin "42") (pinfunction "42_42") (pintype "passive"))
      (node (ref "R17") (pin "1") (pinfunction "1_1") (pintype "passive"))
      (node (ref "R21") (pin "2") (pinfunction "2_2") (pintype "passive"))
      (node (ref "R22") (pin "2") (pinfunction "2_2") (pintype "passive"))
      (node (ref "R23") (pin "2") (pinfunction "2_2") (pintype "passive"))
      (node (ref "R24") (pin "2") (pinfunction "2_2") (pintype "passive"))
      (node (ref "R25") (pin "2") (pinfunction "2_2") (pintype "passive"))
      (node (ref "R26") (pin "2") (pinfunction "2_2") (pintype "passive"))
      (node (ref "R3") (pin "2") (pintype "passive"))
      (node (ref "R5") (pin "1") (pintype "passive"))
      (node (ref "S3") (pin "1") (pinfunction "1_1") (pintype "passive"))
      (node (ref "U1") (pin "1") (pinfunction "GND_1") (pintype "passive"))
      (node (ref "U2") (pin "10") (pinfunction "VSS_5_10") (pintype "power_in"))
      (node (ref "U2") (pin "19") (pinfunction "VSSA_19") (pintype "power_in"))
      (node (ref "U2") (pin "27") (pinfunction "VSS_4_27") (pintype "power_in"))
      (node (ref "U2") (pin "49") (pinfunction "VSS_1_49") (pintype "power_in"))
      (node (ref "U2") (pin "74") (pinfunction "VSS_2_74") (pintype "power_in"))
      (node (ref "U2") (pin "99") (pinfunction "VSS_3_99") (pintype "power_in"))
    )
    (net (code "108") (name "Net-(D1-K)") (class "Default")
      (node (ref "D1") (pin "2") (pinfunction "K_2") (pintype "passive"))
      (node (ref "R3") (pin "1") (pintype "passive"))
    )
    (net (code "109") (name "Net-(D3-A)") (class "Default")
      (node (ref "D3") (pin "1") (pinfunction "A_1") (pintype "passive"))
      (node (ref "R1") (pin "2") (pintype "passive"))
    )
    (net (code "110") (name "Net-(D4-A)") (class "Default")
      (node (ref "D4") (pin "1") (pinfunction "A_1") (pintype "passive"))
      (node (ref "R4") (pin "2") (pintype "passive"))
    )
    (net (code "111") (name "Net-(P2-Pad9)") (class "Default")
      (node (ref "P2") (pin "9") (pintype "passive"))
      (node (ref "R8") (pin "2") (pintype "passive"))
    )
    (net (code "112") (name "Net-(P2-Pad12)") (class "Default")
      (node (ref "P2") (pin "12") (pintype "passive"))
      (node (ref "R9") (pin "2") (pintype "passive"))
    )
    (net (code "113") (name "Net-(P14-CC-PadA5)") (class "Default")
      (node (ref "P14") (pin "A5") (pinfunction "CC_A5") (pintype "bidirectional"))
      (node (ref "R25") (pin "1") (pinfunction "1_1") (pintype "passive"))
    )
    (net (code "114") (name "Net-(P14-CC-PadB5)") (class "Default")
      (node (ref "P14") (pin "B5") (pinfunction "CC_B5") (pintype "bidirectional"))
      (node (ref "R26") (pin "1") (pinfunction "1_1") (pintype "passive"))
    )
    (net (code "115") (name "Net-(P15-CC-PadA5)") (class "Default")
      (node (ref "P15") (pin "A5") (pinfunction "CC_A5") (pintype "bidirectional"))
      (node (ref "R23") (pin "1") (pinfunction "1_1") (pintype "passive"))
    )
    (net (code "116") (name "Net-(P15-CC-PadB5)") (class "Default")
      (node (ref "P15") (pin "B5") (pinfunction "CC_B5") (pintype "bidirectional"))
      (node (ref "R24") (pin "1") (pinfunction "1_1") (pintype "passive"))
    )
    (net (code "117") (name "Net-(R5-Pad2)") (class "Default")
      (node (ref "R5") (pin "2") (pintype "passive"))
      (node (ref "S2") (pin "2") (pinfunction "2_2") (pintype "passive"))
    )
    (net (code "118") (name "Net-(R20-Pad2)") (class "Default")
      (node (ref "R20") (pin "2") (pinfunction "2_2") (pintype "passive"))
      (node (ref "S4") (pin "2") (pinfunction "2_2") (pintype "passive"))
    )
    (net (code "119") (name "Net-(S1-COMMON)") (class "Default")
      (node (ref "F1") (pin "2") (pinfunction "2_2") (pintype "passive"))
      (node (ref "S1") (pin "1") (pinfunction "COMMON_1") (pintype "passive"))
    )
    (net (code "120") (name "Net-(S1-NC)") (class "Default")
      (node (ref "C1") (pin "1") (pinfunction "1_1") (pintype "passive"))
      (node (ref "S1") (pin "2") (pinfunction "NC_2") (pintype "passive"))
      (node (ref "U1") (pin "3") (pinfunction "Vin_3") (pintype "passive"))
    )
    (net (code "121") (name "unconnected-(P2-Pad7)") (class "Default")
      (node (ref "P2") (pin "7") (pintype "passive"))
    )
    (net (code "122") (name "unconnected-(P14-RFU1-PadA8)") (class "Default")
      (node (ref "P14") (pin "A8") (pinfunction "RFU1_A8") (pintype "bidirectional+no_connect"))
    )
    (net (code "123") (name "unconnected-(P14-RFU1-PadB8)") (class "Default")
      (node (ref "P14") (pin "B8") (pinfunction "RFU1_B8") (pintype "bidirectional+no_connect"))
    )
    (net (code "124") (name "unconnected-(P15-RFU1-PadA8)") (class "Default")
      (node (ref "P15") (pin "A8") (pinfunction "RFU1_A8") (pintype "bidirectional+no_connect"))
    )
    (net (code "125") (name "unconnected-(P15-RFU1-PadB8)") (class "Default")
      (node (ref "P15") (pin "B8") (pinfunction "RFU1_B8") (pintype "bidirectional+no_connect"))
    )
    (net (code "126") (name "unconnected-(S1-NO-Pad3)") (class "Default")
      (node (ref "S1") (pin "3") (pinfunction "NO_3") (pintype "passive"))
    )
  )
)
